# Transformer-Recitifer.net
KiCad netlist of a schematic drawn in Altium Designer
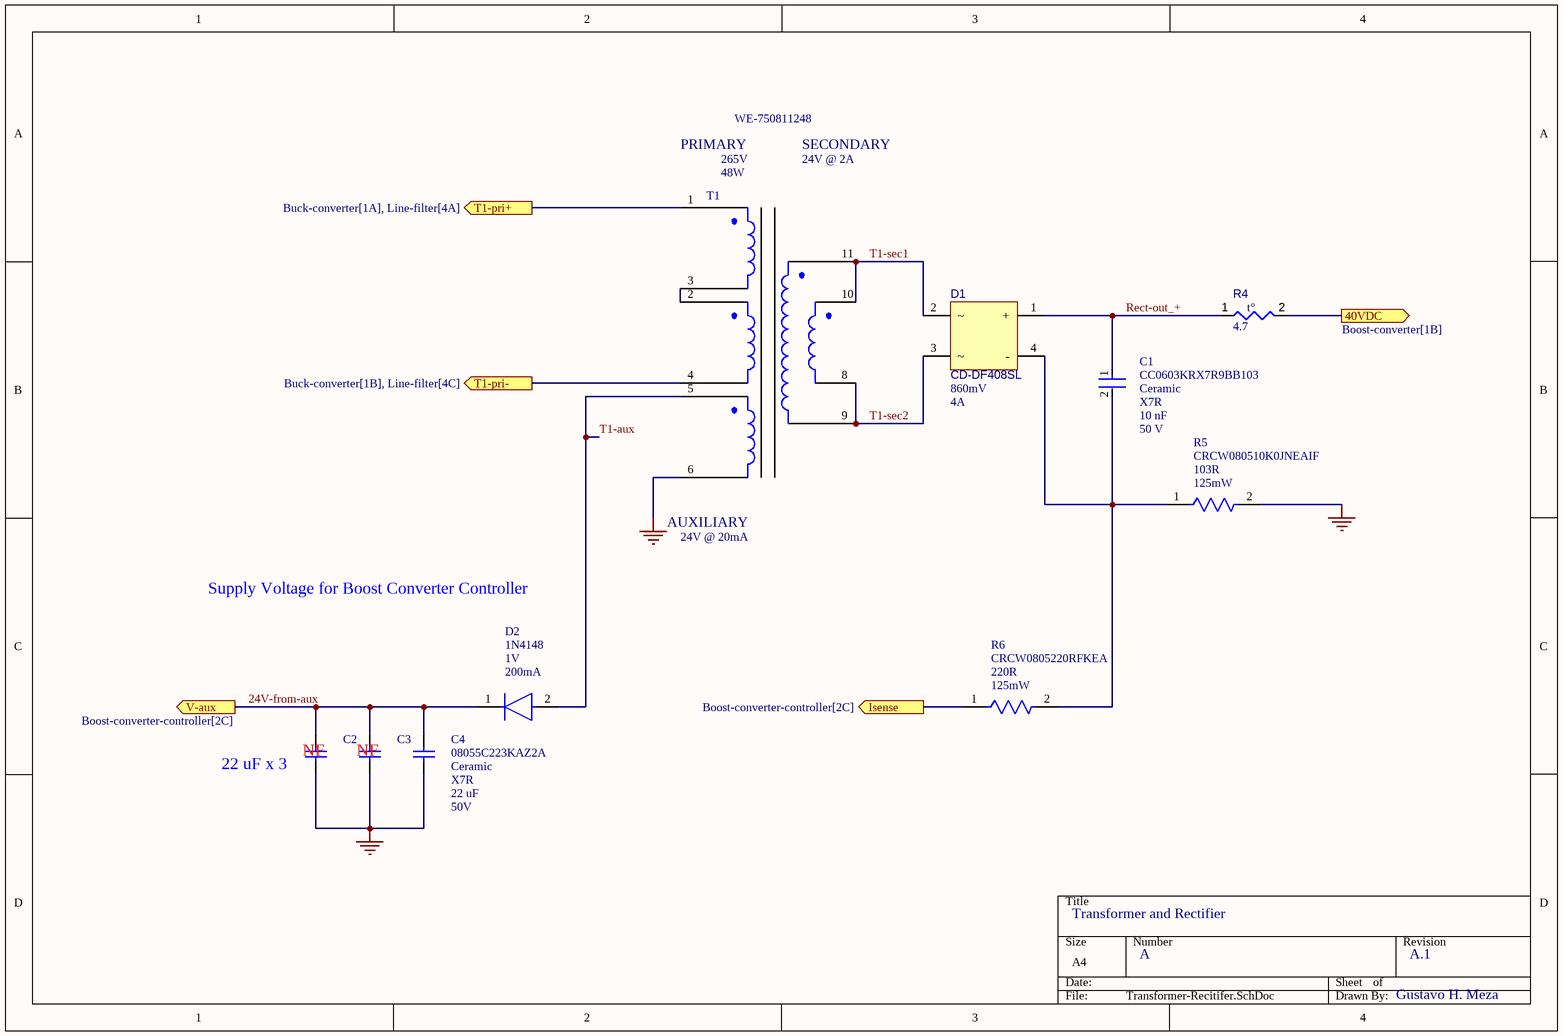
[diagram p0: Transformer-Recitifer.SchDoc]

(export (version "E")
  (design (tool "Eeschema 10.0.6"))
  (components
    (comp (ref "C1")
      (value "CC0603KRX7R9BB103")
      (footprint "FP-CC0603-DA-MFG")
      (description "CAP CER 10000PF 50V X7R 0603")
      (fields
        (field (name "TOLERANCE") "0.1")
        (field (name "TEMPERATURE CHARACTERISTIC") "X7R")
        (field (name "VOLTAGE RATING") "50 V")
        (field (name "MANUFACTURER") "YAGEO")
        (field (name "MATERIAL") "Ceramic")
        (field (name "CAPACITANCE") "10 nF")
      )
      (libsource (lib "Altium Content Vault") (part "11868f565c42a9108669ba33697ecf6"))
    )
    (comp (ref "C2")
      (value "08055C223KAZ2A")
      (footprint "CAPC2013X94X50ML20T25")
      (fields (field (name "MANUFACTURER") "AVX Interconnect / Elco"))
      (libsource (lib "Altium Content Vault") (part "CAP"))
    )
    (comp (ref "C3")
      (value "08055C223KAZ2A")
      (footprint "CAPC2013X94X50ML20T25")
      (fields (field (name "MANUFACTURER") "AVX Interconnect / Elco"))
      (libsource (lib "Altium Content Vault") (part "CAP"))
    )
    (comp (ref "C4")
      (value "08055C223KAZ2A")
      (footprint "CAPC2013X94X50ML20T25")
      (fields
        (field (name "MANUFACTURER") "AVX Interconnect / Elco")
        (field (name "CAPACITANCE") "22 uF")
        (field (name "VOLTAGE RATING") "50V")
        (field (name "DIELEECTRIC") "X7R")
        (field (name "MATERIAL") "Ceramic")
      )
      (libsource (lib "Altium Content Vault") (part "CAP"))
    )
    (comp (ref "D1")
      (value "CD-DF408SL")
      (footprint "CD-DF408SL-Footprint-1")
      (description "Bridge Rectifier Diode, 1 Phase, 4A, 800V V(RRM), Silicon")
      (fields (field (name "FORWARD VOLTAGE") "860mV") (field (name "FORWARD CURRENT") "4A"))
      (libsource (lib "Cetys University") (part "DIODE-2"))
    )
    (comp (ref "D2")
      (value "1N4148")
      (footprint "FP-017AG-MFG")
      (description "DIODE GEN PURP 100V 200MA DO35")
      (fields
        (field (name "FORWARD VOLTAGE") "1V")
        (field (name "OUTPUT CURRENT") "200mA")
        (field (name "VOLTAGE") "100V")
      )
      (libsource (lib "Altium Content Vault") (part "d7152d700b627762746794eb795d46e"))
    )
    (comp (ref "R4")
      (value "4.7")
      (footprint "B57236S0479M000-Footprint-1")
      (description "NTC Thermistor, 4.7ohm, Through Hole Mount")
      (fields (field (name "TOLERANCE") "20%") (field (name "POWER") "2.1W"))
      (libsource (lib "Cetys University") (part "B57236S0479M"))
    )
    (comp (ref "R5")
      (value "CRCW080510K0JNEAIF")
      (footprint "FP-CRCW0805-e3-MFG")
      (description "CRCW080510K0JNEAIF Res Thick Film 0805 10K Ohm 5% 0.125W(1/8W) ±200ppm/°C Pad SMD Automotive T/R")
      (fields
        (field (name "MAX POWER DISSIPATION") "125mW")
        (field (name "RESISTANCE") "103R")
        (field (name "TOLERANCE") "5%")
      )
      (libsource (lib "Altium Content Vault") (part "1029c3af85768c4190bb7ad29bc67b5"))
    )
    (comp (ref "R6")
      (value "CRCW0805220RFKEA")
      (footprint "FP-CRCW0805-e3-MFG")
      (description "RES Thick Film, 220Ω, 1%, 0.125W, 100ppm/°C, 0805")
      (fields
        (field (name "MAX POWER DISSIPATION") "125mW")
        (field (name "RESISTANCE") "220R")
        (field (name "TOLERANCE") "1%")
      )
      (libsource (lib "Altium Content Vault") (part "1029c3af85768c4190bb7ad29bc67b5"))
    )
    (comp (ref "T1")
      (value "WE-750811248")
      (footprint "WE-750811248-Footprint-1")
      (description "Power Transformers MID-L3798/99 Offline Isol 3.6uH +-10%")
      (fields
        (field (name "POWER") "48W")
        (field (name "VOLTAGE RATING") "265V")
        (field (name "AUXILIARY WINDING VOLTAGE") "24V @ 20mA")
        (field (name "SECONDARY WINDING VOLTAGE") "24V @ 2A")
      )
      (libsource (lib "Cetys University") (part "TFORM-4"))
    )
  )
  (nets
    (net (code "1") (name "/24V-from-aux") (class "Default")
      (node (ref "C2") (pin "2") (pinfunction "2_2") (pintype "passive"))
      (node (ref "C3") (pin "2") (pinfunction "2_2") (pintype "passive"))
      (node (ref "C4") (pin "2") (pinfunction "2_2") (pintype "passive"))
      (node (ref "D2") (pin "1") (pinfunction "C_1") (pintype "passive"))
    )
    (net (code "2") (name "/40VDC") (class "Default")
      (node (ref "R4") (pin "2") (pinfunction "2_2") (pintype "passive"))
    )
    (net (code "3") (name "/Isense") (class "Default")
      (node (ref "R6") (pin "1") (pinfunction "1_1") (pintype "passive"))
    )
    (net (code "4") (name "/Rect-out_+") (class "Default")
      (node (ref "C1") (pin "1") (pinfunction "1_1") (pintype "passive"))
      (node (ref "D1") (pin "1") (pinfunction "+_1") (pintype "passive"))
      (node (ref "R4") (pin "1") (pinfunction "1_1") (pintype "passive"))
    )
    (net (code "5") (name "/T1-aux") (class "Default")
      (node (ref "D2") (pin "2") (pinfunction "A_2") (pintype "passive"))
      (node (ref "T1") (pin "5") (pinfunction "5_5") (pintype "passive"))
    )
    (net (code "6") (name "/T1-pri+") (class "Default")
      (node (ref "T1") (pin "1") (pinfunction "1_1") (pintype "passive"))
    )
    (net (code "7") (name "/T1-pri-") (class "Default")
      (node (ref "T1") (pin "4") (pinfunction "4_4") (pintype "passive"))
    )
    (net (code "8") (name "/T1-sec1") (class "Default")
      (node (ref "D1") (pin "2") (pinfunction "~_2") (pintype "passive"))
      (node (ref "T1") (pin "10") (pinfunction "10_10") (pintype "passive"))
      (node (ref "T1") (pin "11") (pinfunction "11_11") (pintype "passive"))
    )
    (net (code "9") (name "/T1-sec2") (class "Default")
      (node (ref "D1") (pin "3") (pinfunction "~_3") (pintype "passive"))
      (node (ref "T1") (pin "8") (pinfunction "8_8") (pintype "passive"))
      (node (ref "T1") (pin "9") (pinfunction "9_9") (pintype "passive"))
    )
    (net (code "10") (name "GND") (class "Default")
      (node (ref "C2") (pin "1") (pinfunction "1_1") (pintype "passive"))
      (node (ref "C3") (pin "1") (pinfunction "1_1") (pintype "passive"))
      (node (ref "C4") (pin "1") (pinfunction "1_1") (pintype "passive"))
      (node (ref "R5") (pin "2") (pinfunction "2_2") (pintype "passive"))
      (node (ref "T1") (pin "6") (pinfunction "6_6") (pintype "passive"))
    )
    (net (code "11") (name "Net-(D1--)") (class "Default")
      (node (ref "C1") (pin "2") (pinfunction "2_2") (pintype "passive"))
      (node (ref "D1") (pin "4") (pinfunction "-_4") (pintype "passive"))
      (node (ref "R5") (pin "1") (pinfunction "1_1") (pintype "passive"))
      (node (ref "R6") (pin "2") (pinfunction "2_2") (pintype "passive"))
    )
    (net (code "12") (name "Net-(T1-Pad2)_1") (class "Default")
      (node (ref "T1") (pin "2") (pinfunction "2_2") (pintype "passive"))
      (node (ref "T1") (pin "3") (pinfunction "3_3") (pintype "passive"))
    )
    (net (code "13") (name "unconnected-(T1-Pad1)") (class "Default")
      (node (ref "T1") (pin "1") (pinfunction "1_1") (pintype "passive"))
    )
    (net (code "14") (name "unconnected-(T1-Pad1)_1") (class "Default")
      (node (ref "T1") (pin "1") (pinfunction "1_1") (pintype "passive"))
    )
    (net (code "15") (name "unconnected-(T1-Pad1)_2") (class "Default")
      (node (ref "T1") (pin "1") (pinfunction "1_1") (pintype "passive"))
    )
    (net (code "16") (name "unconnected-(T1-Pad1)_3") (class "Default")
      (node (ref "T1") (pin "1") (pinfunction "1_1") (pintype "passive"))
    )
    (net (code "17") (name "unconnected-(T1-Pad2)") (class "Default")
      (node (ref "T1") (pin "2") (pinfunction "2_2") (pintype "passive"))
    )
    (net (code "18") (name "unconnected-(T1-Pad2)_2") (class "Default")
      (node (ref "T1") (pin "2") (pinfunction "2_2") (pintype "passive"))
    )
    (net (code "19") (name "unconnected-(T1-Pad2)_3") (class "Default")
      (node (ref "T1") (pin "2") (pinfunction "2_2") (pintype "passive"))
    )
    (net (code "20") (name "unconnected-(T1-Pad2)_4") (class "Default")
      (node (ref "T1") (pin "2") (pinfunction "2_2") (pintype "passive"))
    )
    (net (code "21") (name "unconnected-(T1-Pad3)") (class "Default")
      (node (ref "T1") (pin "3") (pinfunction "3_3") (pintype "passive"))
    )
    (net (code "22") (name "unconnected-(T1-Pad4)") (class "Default")
      (node (ref "T1") (pin "4") (pinfunction "4_4") (pintype "passive"))
    )
  )
)
